# fonte.net
KiCad netlist of a schematic drawn in EAGLE
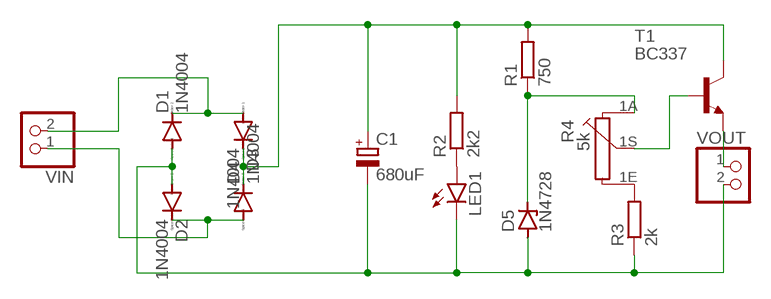
[diagram p0: schematic, sheet 1]

(export (version "E")
  (design (tool "Eeschema 10.0.6"))
  (components
    (comp (ref "C1")
      (value "680uF")
      (footprint "eagle-import:PANASONIC_D")
      (libsource (lib "eagle-import") (part "CPOL-EUD"))
    )
    (comp (ref "D1")
      (value "1N4004")
      (footprint "eagle-import:DO41-10")
      (libsource (lib "eagle-import") (part "1N4004"))
    )
    (comp (ref "D2")
      (value "1N4004")
      (footprint "eagle-import:DO41-10")
      (libsource (lib "eagle-import") (part "1N4004"))
    )
    (comp (ref "D3")
      (value "1N4004")
      (footprint "eagle-import:DO41-10")
      (libsource (lib "eagle-import") (part "1N4004"))
    )
    (comp (ref "D4")
      (value "1N4004")
      (footprint "eagle-import:DO41-10")
      (libsource (lib "eagle-import") (part "1N4004"))
    )
    (comp (ref "D5")
      (value "1N4728")
      (footprint "eagle-import:DO41Z10")
      (libsource (lib "eagle-import") (part "1N4728"))
    )
    (comp (ref "LED1")
      (value "LED5MM")
      (footprint "eagle-import:LED5MM")
      (libsource (lib "eagle-import") (part "LED5MM"))
    )
    (comp (ref "R1")
      (value "750")
      (footprint "eagle-import:0207_10")
      (libsource (lib "eagle-import") (part "R-EU_0207/10"))
    )
    (comp (ref "R2")
      (value "2k2")
      (footprint "eagle-import:0207_10")
      (libsource (lib "eagle-import") (part "R-EU_0207/10"))
    )
    (comp (ref "R3")
      (value "2k")
      (footprint "eagle-import:0207_10")
      (libsource (lib "eagle-import") (part "R-EU_0207/10"))
    )
    (comp (ref "R4")
      (value "5k")
      (footprint "eagle-import:PC16S")
      (libsource (lib "eagle-import") (part "PC16S"))
    )
    (comp (ref "T1")
      (value "BC337")
      (footprint "eagle-import:TO92")
      (libsource (lib "eagle-import") (part "BC337"))
    )
    (comp (ref "VIN")
      (value "PINHD-1X2")
      (footprint "eagle-import:1X02")
      (libsource (lib "eagle-import") (part "PINHD-1X2"))
    )
    (comp (ref "VOUT")
      (value "PINHD-1X2")
      (footprint "eagle-import:1X02")
      (libsource (lib "eagle-import") (part "PINHD-1X2"))
    )
  )
  (nets
    (net (code "1") (name "Net-(D1-PadC)") (class "Default")
      (node (ref "D1") (pin "C") (pinfunction "C_C") (pintype "passive"))
      (node (ref "D3") (pin "A") (pinfunction "A_A") (pintype "passive"))
      (node (ref "VIN") (pin "2") (pinfunction "2_2") (pintype "passive"))
    )
    (net (code "2") (name "Net-(D2-PadC)") (class "Default")
      (node (ref "D2") (pin "C") (pinfunction "C_C") (pintype "passive"))
      (node (ref "D4") (pin "A") (pinfunction "A_A") (pintype "passive"))
      (node (ref "VIN") (pin "1") (pinfunction "1_1") (pintype "passive"))
    )
    (net (code "3") (name "Net-(D5-PadC)") (class "Default")
      (node (ref "D5") (pin "C") (pinfunction "C_C") (pintype "passive"))
      (node (ref "R1") (pin "1") (pinfunction "1_1") (pintype "passive"))
      (node (ref "R4") (pin "1A") (pinfunction "1A_1A") (pintype "passive"))
    )
    (net (code "4") (name "Net-(LED1-C)") (class "Default")
      (node (ref "C1") (pin "-") (pinfunction "-_-") (pintype "passive"))
      (node (ref "D1") (pin "A") (pinfunction "A_A") (pintype "passive"))
      (node (ref "D2") (pin "A") (pinfunction "A_A") (pintype "passive"))
      (node (ref "D5") (pin "A") (pinfunction "A_A") (pintype "passive"))
      (node (ref "LED1") (pin "K") (pinfunction "C_K") (pintype "passive"))
      (node (ref "R3") (pin "1") (pinfunction "1_1") (pintype "passive"))
      (node (ref "VOUT") (pin "2") (pinfunction "2_2") (pintype "passive"))
    )
    (net (code "5") (name "Net-(LED1-PadA)") (class "Default")
      (node (ref "LED1") (pin "A") (pinfunction "A_A") (pintype "passive"))
      (node (ref "R2") (pin "1") (pinfunction "1_1") (pintype "passive"))
    )
    (net (code "6") (name "Net-(R3-Pad2)") (class "Default")
      (node (ref "R3") (pin "2") (pinfunction "2_2") (pintype "passive"))
      (node (ref "R4") (pin "1E") (pinfunction "1E_1E") (pintype "passive"))
    )
    (net (code "7") (name "Net-(T1-B)") (class "Default")
      (node (ref "R4") (pin "1S") (pinfunction "1S_1S") (pintype "passive"))
      (node (ref "T1") (pin "2") (pinfunction "B_2") (pintype "passive"))
    )
    (net (code "8") (name "Net-(T1-C)") (class "Default")
      (node (ref "C1") (pin "+") (pinfunction "+_+") (pintype "passive"))
      (node (ref "D3") (pin "C") (pinfunction "C_C") (pintype "passive"))
      (node (ref "D4") (pin "C") (pinfunction "C_C") (pintype "passive"))
      (node (ref "R1") (pin "2") (pinfunction "2_2") (pintype "passive"))
      (node (ref "R2") (pin "2") (pinfunction "2_2") (pintype "passive"))
      (node (ref "T1") (pin "3") (pinfunction "C_3") (pintype "passive"))
    )
    (net (code "9") (name "Net-(T1-E)") (class "Default")
      (node (ref "T1") (pin "1") (pinfunction "E_1") (pintype "passive"))
      (node (ref "VOUT") (pin "1") (pinfunction "1_1") (pintype "passive"))
    )
  )
)
